# differential_driver.net
KiCad netlist of a schematic drawn in Altium Designer
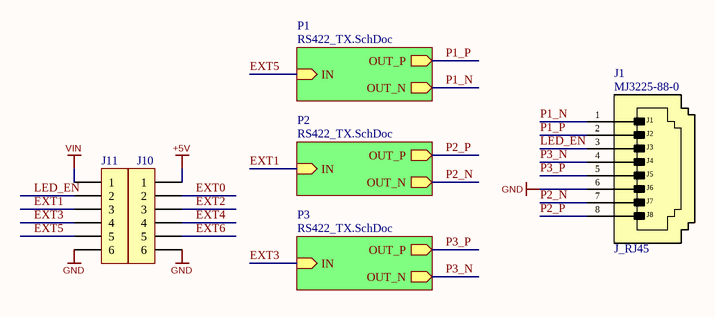
[diagram p0: differential driver.SchDoc]

(export (version "E")
  (design (tool "Eeschema 10.0.6"))
  (components
    (comp (ref "J1")
      (value "MJ3225-88-0")
      (footprint "J_RJ45_MJ3225-88-0")
      (fields
        (field (name "SCH_FOOTPRINT") "J_RJ45")
        (field (name "PART NUMBER") "J_RJ45_MJ3225-88-0")
        (field (name "MANUFACTURER") "Global Connector Technology")
        (field (name "Comment") "Modular Connector, Modular Jack, 1 x 1 (Port), 8P8C, Cat3")
      )
      (libsource (lib "Library") (part "J_RJ45"))
    )
    (comp (ref "J10")
      (value "Goldpin")
      (footprint "P_HEADER_1x6_2.54")
      (description "Pin Header")
      (fields (field (name "PART NUMBER") "P_HEADER_1x6_2.54") (field (name "MANUFACTURER") "Connfly"))
      (libsource (lib "Library") (part "P_HEADER_1x6"))
    )
    (comp (ref "J11")
      (value "Goldpin")
      (footprint "P_HEADER_1x6_2.54")
      (description "Pin Header")
      (fields (field (name "PART NUMBER") "P_HEADER_1x6_2.54") (field (name "MANUFACTURER") "Connfly"))
      (libsource (lib "") (part "P_HEADER_1x6_1"))
    )
  )
  (nets
    (net (code "1") (name "+5V") (class "Default")
      (node (ref "J10") (pin "1") (pinfunction "1_1") (pintype "passive"))
    )
    (net (code "2") (name "/EXT0") (class "Default")
      (node (ref "J10") (pin "2") (pinfunction "2_2") (pintype "passive"))
    )
    (net (code "3") (name "/EXT1") (class "Default")
      (node (ref "J11") (pin "3") (pinfunction "3_3") (pintype "passive"))
    )
    (net (code "4") (name "/EXT2") (class "Default")
      (node (ref "J10") (pin "3") (pinfunction "3_3") (pintype "passive"))
    )
    (net (code "5") (name "/EXT3") (class "Default")
      (node (ref "J11") (pin "4") (pinfunction "4_4") (pintype "passive"))
    )
    (net (code "6") (name "/EXT4") (class "Default")
      (node (ref "J10") (pin "4") (pinfunction "4_4") (pintype "passive"))
    )
    (net (code "7") (name "/EXT5") (class "Default")
      (node (ref "J11") (pin "5") (pinfunction "5_5") (pintype "passive"))
    )
    (net (code "8") (name "/EXT6") (class "Default")
      (node (ref "J10") (pin "5") (pinfunction "5_5") (pintype "passive"))
    )
    (net (code "9") (name "/LED_EN") (class "Default")
      (node (ref "J1") (pin "3") (pintype "passive"))
      (node (ref "J11") (pin "2") (pinfunction "2_2") (pintype "passive"))
    )
    (net (code "10") (name "/P1_N") (class "Default") (node (ref "J1") (pin "1") (pintype "passive")))
    (net (code "11") (name "/P1_P") (class "Default") (node (ref "J1") (pin "2") (pintype "passive")))
    (net (code "12") (name "/P2_N") (class "Default") (node (ref "J1") (pin "7") (pintype "passive")))
    (net (code "13") (name "/P2_P") (class "Default") (node (ref "J1") (pin "8") (pintype "passive")))
    (net (code "14") (name "/P3_N") (class "Default") (node (ref "J1") (pin "4") (pintype "passive")))
    (net (code "15") (name "/P3_P") (class "Default") (node (ref "J1") (pin "5") (pintype "passive")))
    (net (code "16") (name "GND") (class "Default")
      (node (ref "J1") (pin "6") (pintype "passive"))
      (node (ref "J10") (pin "6") (pinfunction "6_6") (pintype "passive"))
      (node (ref "J11") (pin "6") (pinfunction "6_6") (pintype "passive"))
    )
    (net (code "17") (name "VIN") (class "Default")
      (node (ref "J11") (pin "1") (pinfunction "1_1") (pintype "passive"))
    )
  )
)
